# main.net
KiCad netlist of a schematic drawn in Altium Designer
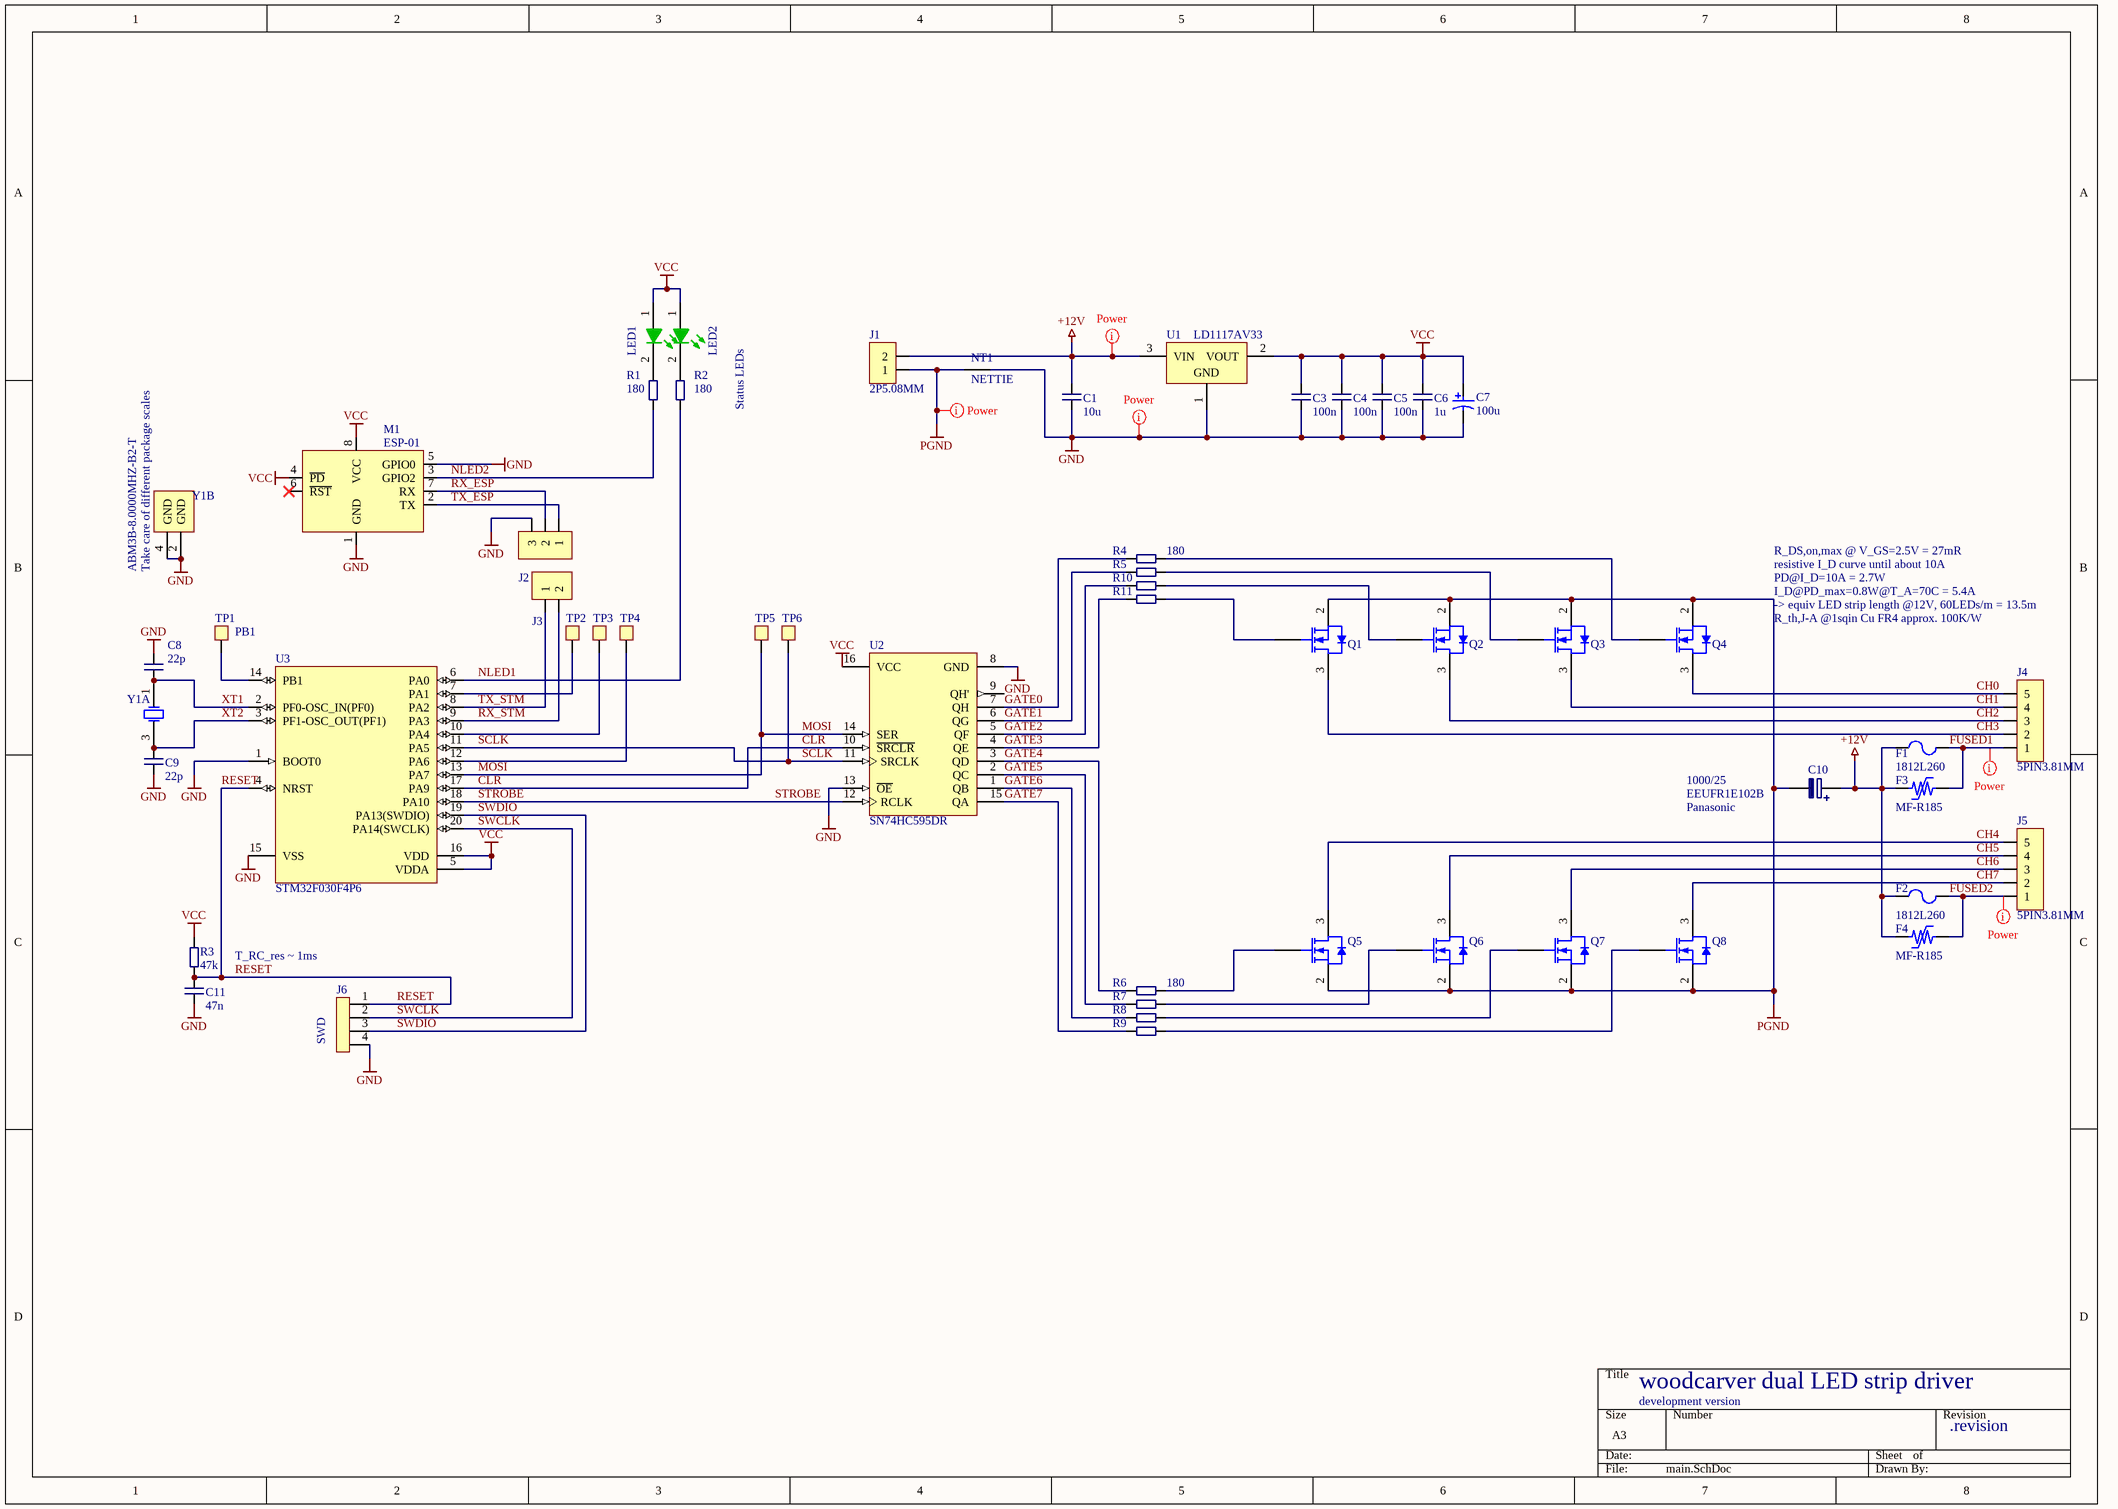
[diagram p0: main.SchDoc]

(export (version "E")
  (design (tool "Eeschema 10.0.6"))
  (components
    (comp (ref "C1")
      (value "10u")
      (footprint "6-0805_M")
      (description "Capacitor")
      (libsource (lib "components") (part "C"))
    )
    (comp (ref "C3")
      (value "100n")
      (footprint "J1-0603")
      (description "Capacitor")
      (libsource (lib "components") (part "C"))
    )
    (comp (ref "C4")
      (value "100n")
      (footprint "J1-0603")
      (description "Capacitor")
      (libsource (lib "components") (part "C"))
    )
    (comp (ref "C5")
      (value "100n")
      (footprint "J1-0603")
      (description "Capacitor")
      (libsource (lib "components") (part "C"))
    )
    (comp (ref "C6")
      (value "1u")
      (footprint "6-0805_M")
      (description "Capacitor")
      (libsource (lib "components") (part "C"))
    )
    (comp (ref "C7")
      (value "100u")
      (footprint "FHTE-8-AA07-2_L")
      (fields
        (field (name "MANUFACTURER") "Fenghuang Technology")
        (field (name "PARTNUMBER") "8471LCJAA07WPN081T")
        (field (name "TOLERANCE") "+/- 5%")
      )
      (libsource (lib "Altium Content Vault") (part "FHTE-CAP-P-2"))
    )
    (comp (ref "C8")
      (value "22p")
      (footprint "J1-0603")
      (description "Capacitor")
      (libsource (lib "components") (part "C"))
    )
    (comp (ref "C9")
      (value "22p")
      (footprint "J1-0603")
      (description "Capacitor")
      (libsource (lib "components") (part "C"))
    )
    (comp (ref "C10")
      (value "1000/25")
      (footprint "ELKO_10MM_RM5_SIDE_25MM")
      (fields (field (name "MFG PART NO") "EEUFR1E102B") (field (name "MFG") "Panasonic"))
      (libsource (lib "components") (part "ELKO"))
    )
    (comp (ref "C11")
      (value "47n")
      (footprint "J1-0603")
      (description "Capacitor")
      (libsource (lib "components") (part "C"))
    )
    (comp (ref "F1")
      (value "1812L260")
      (footprint "LFUS-FUSE1812-71_V")
      (description "Resettable PTC, 1812, 1.5 A Ihold, 3.0 A Itrip")
      (fields (field (name "PARTNUMBER") "1812L150ZR"))
      (libsource (lib "Altium Content Vault") (part "LFUS-FUSE-2"))
    )
    (comp (ref "F2")
      (value "1812L260")
      (footprint "LFUS-FUSE1812-71_V")
      (description "Resettable PTC, 1812, 1.5 A Ihold, 3.0 A Itrip")
      (fields (field (name "PARTNUMBER") "1812L150ZR"))
      (libsource (lib "Altium Content Vault") (part "LFUS-FUSE-2"))
    )
    (comp (ref "F3")
      (value "MF-R185")
      (footprint "BOUR-MF-R185")
      (description "PTC Resettable Fuse, 30 V, 40 A, -40 to 85 degC, 2-Pin THD, RoHS, Bulk")
      (fields (field (name "MANUFACTURER") "Bourns"))
      (libsource (lib "Altium Content Vault") (part "PPTC-2"))
    )
    (comp (ref "F4")
      (value "MF-R185")
      (footprint "BOUR-MF-R185")
      (description "PTC Resettable Fuse, 30 V, 40 A, -40 to 85 degC, 2-Pin THD, RoHS, Bulk")
      (fields (field (name "MANUFACTURER") "Bourns"))
      (libsource (lib "Altium Content Vault") (part "PPTC-2"))
    )
    (comp (ref "J1")
      (value "2P5.08MM")
      (footprint "HEADER_2PIN_RM5.08MM_PLUGGABLE")
      (description "Pluggable Header 2 Pin RM 5.08mm ~15A")
      (libsource (lib "components") (part "PHD2P5.08RM"))
    )
    (comp (ref "J2")
      (value "PINHD_1x3_2.54MM")
      (footprint "PINHD_3X1_2.54MM")
      (description "Pin Header 1 row 3 pin RM 2.54mm")
      (libsource (lib "components") (part "PINHD1X3"))
    )
    (comp (ref "J3")
      (value "PINHD_1x2_2.54MM")
      (footprint "PINHD_2X1_2.54MM")
      (description "Pin Header 1 row 2 pin RM 2.54mm")
      (libsource (lib "components") (part "PINHD1X2"))
    )
    (comp (ref "J4")
      (value "5PIN3.81MM")
      (footprint "HEADER_5PIN_RM3.81MM_PLUGGABLE")
      (description "Pluggable Header 5 Pin RM 3.81mm ~8A")
      (libsource (lib "components") (part "PHD5P3.81RM"))
    )
    (comp (ref "J5")
      (value "5PIN3.81MM")
      (footprint "HEADER_5PIN_RM3.81MM_PLUGGABLE")
      (description "Pluggable Header 5 Pin RM 3.81mm ~8A")
      (libsource (lib "components") (part "PHD5P3.81RM"))
    )
    (comp (ref "J6")
      (value "SWD")
      (footprint "PINHD_4X1_2.54MM")
      (description "Pin Header 4x1 pin")
      (libsource (lib "components") (part "PH_4x1"))
    )
    (comp (ref "LED1")
      (value "KP-1608MGC")
      (footprint "KING-0603LED_GREEN_V")
      (description "LED, SMT, 0603(1608), 1.1mm thickness, Green")
      (fields (field (name "MANUFACTURER") "Kingbright"))
      (libsource (lib "components") (part "CMP-0404-00001-1"))
    )
    (comp (ref "LED2")
      (value "KP-1608MGC")
      (footprint "KING-0603LED_GREEN_V")
      (description "LED, SMT, 0603(1608), 1.1mm thickness, Green")
      (fields (field (name "MANUFACTURER") "Kingbright"))
      (libsource (lib "components") (part "CMP-0404-00001-1"))
    )
    (comp (ref "M1")
      (value "ESP-01")
      (footprint "ESP01")
      (description "ESP-01 ESP8266 Wifi Module")
      (libsource (lib "components") (part "ESP01"))
    )
    (comp (ref "NT1") (value "NETTIE") (footprint "NETTIE") (libsource (lib "components") (part "NETTIE")))
    (comp (ref "Q1")
      (value "IRLML6244TRPbF")
      (footprint "ONSC-SOT-23-3-318-08_V")
      (description "Power MOSFET, 500 mA, 60 V, N-Channel, 3-Pin SOT-23, Pb-Free, Tape and Reel")
      (fields (field (name "MANUFACTURER") "On Semiconductor") (field (name "PARTNUMBER") "NVBF170LT1G"))
      (libsource (lib "Altium Content Vault") (part "ONSC-NMOS-G1S2D3-3"))
    )
    (comp (ref "Q2")
      (value "IRLML6244TRPbF")
      (footprint "ONSC-SOT-23-3-318-08_V")
      (description "Power MOSFET, 500 mA, 60 V, N-Channel, 3-Pin SOT-23, Pb-Free, Tape and Reel")
      (fields (field (name "MANUFACTURER") "On Semiconductor") (field (name "PARTNUMBER") "NVBF170LT1G"))
      (libsource (lib "Altium Content Vault") (part "ONSC-NMOS-G1S2D3-3"))
    )
    (comp (ref "Q3")
      (value "IRLML6244TRPbF")
      (footprint "ONSC-SOT-23-3-318-08_V")
      (description "Power MOSFET, 500 mA, 60 V, N-Channel, 3-Pin SOT-23, Pb-Free, Tape and Reel")
      (fields (field (name "MANUFACTURER") "On Semiconductor") (field (name "PARTNUMBER") "NVBF170LT1G"))
      (libsource (lib "Altium Content Vault") (part "ONSC-NMOS-G1S2D3-3"))
    )
    (comp (ref "Q4")
      (value "IRLML6244TRPbF")
      (footprint "ONSC-SOT-23-3-318-08_V")
      (description "Power MOSFET, 500 mA, 60 V, N-Channel, 3-Pin SOT-23, Pb-Free, Tape and Reel")
      (fields (field (name "MANUFACTURER") "On Semiconductor") (field (name "PARTNUMBER") "NVBF170LT1G"))
      (libsource (lib "Altium Content Vault") (part "ONSC-NMOS-G1S2D3-3"))
    )
    (comp (ref "Q5")
      (value "IRLML6244TRPbF")
      (footprint "ONSC-SOT-23-3-318-08_V")
      (description "Power MOSFET, 500 mA, 60 V, N-Channel, 3-Pin SOT-23, Pb-Free, Tape and Reel")
      (fields (field (name "MANUFACTURER") "On Semiconductor") (field (name "PARTNUMBER") "NVBF170LT1G"))
      (libsource (lib "Altium Content Vault") (part "ONSC-NMOS-G1S2D3-3"))
    )
    (comp (ref "Q6")
      (value "IRLML6244TRPbF")
      (footprint "ONSC-SOT-23-3-318-08_V")
      (description "Power MOSFET, 500 mA, 60 V, N-Channel, 3-Pin SOT-23, Pb-Free, Tape and Reel")
      (fields (field (name "MANUFACTURER") "On Semiconductor") (field (name "PARTNUMBER") "NVBF170LT1G"))
      (libsource (lib "Altium Content Vault") (part "ONSC-NMOS-G1S2D3-3"))
    )
    (comp (ref "Q7")
      (value "IRLML6244TRPbF")
      (footprint "ONSC-SOT-23-3-318-08_V")
      (description "Power MOSFET, 500 mA, 60 V, N-Channel, 3-Pin SOT-23, Pb-Free, Tape and Reel")
      (fields (field (name "MANUFACTURER") "On Semiconductor") (field (name "PARTNUMBER") "NVBF170LT1G"))
      (libsource (lib "Altium Content Vault") (part "ONSC-NMOS-G1S2D3-3"))
    )
    (comp (ref "Q8")
      (value "IRLML6244TRPbF")
      (footprint "ONSC-SOT-23-3-318-08_V")
      (description "Power MOSFET, 500 mA, 60 V, N-Channel, 3-Pin SOT-23, Pb-Free, Tape and Reel")
      (fields (field (name "MANUFACTURER") "On Semiconductor") (field (name "PARTNUMBER") "NVBF170LT1G"))
      (libsource (lib "Altium Content Vault") (part "ONSC-NMOS-G1S2D3-3"))
    )
    (comp (ref "R1")
      (value "180")
      (footprint "J1-0603")
      (description "Resistor")
      (libsource (lib "components") (part "R"))
    )
    (comp (ref "R2")
      (value "180")
      (footprint "J1-0603")
      (description "Resistor")
      (libsource (lib "components") (part "R"))
    )
    (comp (ref "R3")
      (value "47k")
      (footprint "J1-0603")
      (description "Resistor")
      (libsource (lib "components") (part "R"))
    )
    (comp (ref "R4")
      (value "180")
      (footprint "J1-0603")
      (description "Resistor")
      (libsource (lib "components") (part "R"))
    )
    (comp (ref "R5")
      (value "180")
      (footprint "J1-0603")
      (description "Resistor")
      (libsource (lib "components") (part "R"))
    )
    (comp (ref "R6")
      (value "180")
      (footprint "J1-0603")
      (description "Resistor")
      (libsource (lib "components") (part "R"))
    )
    (comp (ref "R7")
      (value "180")
      (footprint "J1-0603")
      (description "Resistor")
      (libsource (lib "components") (part "R"))
    )
    (comp (ref "R8")
      (value "180")
      (footprint "J1-0603")
      (description "Resistor")
      (libsource (lib "components") (part "R"))
    )
    (comp (ref "R9")
      (value "180")
      (footprint "J1-0603")
      (description "Resistor")
      (libsource (lib "components") (part "R"))
    )
    (comp (ref "R10")
      (value "180")
      (footprint "J1-0603")
      (description "Resistor")
      (libsource (lib "components") (part "R"))
    )
    (comp (ref "R11")
      (value "180")
      (footprint "J1-0603")
      (description "Resistor")
      (libsource (lib "components") (part "R"))
    )
    (comp (ref "TP1")
      (value "PB1")
      (footprint "TESTPOINT_2mm")
      (description "Testpoint")
      (libsource (lib "components") (part "TESTPOINT"))
    )
    (comp (ref "TP2")
      (value "PA1")
      (footprint "TESTPOINT_2mm")
      (description "Testpoint")
      (libsource (lib "components") (part "TESTPOINT"))
    )
    (comp (ref "TP3")
      (value "PA4")
      (footprint "TESTPOINT_2mm")
      (description "Testpoint")
      (libsource (lib "components") (part "TESTPOINT"))
    )
    (comp (ref "TP4")
      (value "PA6")
      (footprint "TESTPOINT_2mm")
      (description "Testpoint")
      (libsource (lib "components") (part "TESTPOINT"))
    )
    (comp (ref "TP5")
      (value "PA6")
      (footprint "TESTPOINT_2mm")
      (description "Testpoint")
      (libsource (lib "components") (part "TESTPOINT"))
    )
    (comp (ref "TP6")
      (value "PA6")
      (footprint "TESTPOINT_2mm")
      (description "Testpoint")
      (libsource (lib "components") (part "TESTPOINT"))
    )
    (comp (ref "U1")
      (value "LD1117AV33")
      (footprint "TO220")
      (description "1A, Low Drop Positive Voltage Regulator, 3.3V, 3-Pin TO-220")
      (libsource (lib "Altium Content Vault") (part "PM-REG-LD1117V-SIL3"))
    )
    (comp (ref "U2")
      (value "SN74HC595DR")
      (footprint "D0016A_M")
      (description "8-Bit Shift Registers With 3-State Output Registers, D0016A, LARGE T&R")
      (fields
        (field (name "GENERIC PART NUMBER") "SN74HC595")
        (field (name "MANUFACTURER") "Texas Instruments")
      )
      (libsource (lib "Altium Content Vault") (part "CMP-0780-00037-3"))
    )
    (comp (ref "U3")
      (value "STM32F030F4P6")
      (footprint "STM-TSSOP20_L")
      (libsource (lib "Altium Content Vault") (part "MC-ARM-STM32F030-IL20"))
    )
    (comp (ref "Y1")
      (value "ABM3B-8.0000MHZ-B2-T")
      (footprint "XTAL_MJ_5x3.2")
      (description "Crystal, SMD, 25.000000MHz Stab=50ppm 18.0pF")
      (fields
        (field (name "MANUFACTURER") "Abracon")
        (field (name "PARTNUMBER") "ABM3B-25.000MHZ-B2-T")
        (field (name "NOTE") "Take care of different package scales")
      )
      (libsource (lib "components") (part "ABRA-ABM3B-4"))
    )
  )
  (nets
    (net (code "1") (name "+12V") (class "Default")
      (node (ref "C1") (pin "1") (pinfunction "1_1") (pintype "passive"))
      (node (ref "C10") (pin "1") (pinfunction "1_1") (pintype "passive"))
      (node (ref "F1") (pin "1") (pinfunction "1_1") (pintype "passive"))
      (node (ref "F2") (pin "1") (pinfunction "1_1") (pintype "passive"))
      (node (ref "F3") (pin "1") (pinfunction "1_1") (pintype "passive"))
      (node (ref "F4") (pin "1") (pinfunction "1_1") (pintype "passive"))
      (node (ref "J1") (pin "2") (pinfunction "2_2") (pintype "passive"))
      (node (ref "U1") (pin "3") (pinfunction "VIN_3") (pintype "power_in"))
    )
    (net (code "2") (name "/CH0") (class "Default")
      (node (ref "J4") (pin "5") (pinfunction "5_5") (pintype "passive"))
      (node (ref "Q4") (pin "3") (pinfunction "D_3") (pintype "passive"))
    )
    (net (code "3") (name "/CH1") (class "Default")
      (node (ref "J4") (pin "4") (pinfunction "4_4") (pintype "passive"))
      (node (ref "Q3") (pin "3") (pinfunction "D_3") (pintype "passive"))
    )
    (net (code "4") (name "/CH2") (class "Default")
      (node (ref "J4") (pin "3") (pinfunction "3_3") (pintype "passive"))
      (node (ref "Q2") (pin "3") (pinfunction "D_3") (pintype "passive"))
    )
    (net (code "5") (name "/CH3") (class "Default")
      (node (ref "J4") (pin "2") (pinfunction "2_2") (pintype "passive"))
      (node (ref "Q1") (pin "3") (pinfunction "D_3") (pintype "passive"))
    )
    (net (code "6") (name "/CH4") (class "Default")
      (node (ref "J5") (pin "5") (pinfunction "5_5") (pintype "passive"))
      (node (ref "Q5") (pin "3") (pinfunction "D_3") (pintype "passive"))
    )
    (net (code "7") (name "/CH5") (class "Default")
      (node (ref "J5") (pin "4") (pinfunction "4_4") (pintype "passive"))
      (node (ref "Q6") (pin "3") (pinfunction "D_3") (pintype "passive"))
    )
    (net (code "8") (name "/CH6") (class "Default")
      (node (ref "J5") (pin "3") (pinfunction "3_3") (pintype "passive"))
      (node (ref "Q7") (pin "3") (pinfunction "D_3") (pintype "passive"))
    )
    (net (code "9") (name "/CH7") (class "Default")
      (node (ref "J5") (pin "2") (pinfunction "2_2") (pintype "passive"))
      (node (ref "Q8") (pin "3") (pinfunction "D_3") (pintype "passive"))
    )
    (net (code "10") (name "/CLR") (class "Default")
      (node (ref "U2") (pin "10") (pinfunction "~{SRCLR}_10") (pintype "input"))
      (node (ref "U3") (pin "17") (pinfunction "PA9_17") (pintype "bidirectional"))
    )
    (net (code "11") (name "/FUSED1") (class "Default")
      (node (ref "F1") (pin "2") (pinfunction "2_2") (pintype "passive"))
      (node (ref "F3") (pin "2") (pinfunction "2_2") (pintype "passive"))
      (node (ref "J4") (pin "1") (pinfunction "1_1") (pintype "passive"))
    )
    (net (code "12") (name "/FUSED2") (class "Default")
      (node (ref "F2") (pin "2") (pinfunction "2_2") (pintype "passive"))
      (node (ref "F4") (pin "2") (pinfunction "2_2") (pintype "passive"))
      (node (ref "J5") (pin "1") (pinfunction "1_1") (pintype "passive"))
    )
    (net (code "13") (name "/GATE0") (class "Default")
      (node (ref "R4") (pin "2") (pinfunction "2_2") (pintype "passive"))
      (node (ref "U2") (pin "7") (pinfunction "QH_7") (pintype "tri_state"))
    )
    (net (code "14") (name "/GATE1") (class "Default")
      (node (ref "R5") (pin "2") (pinfunction "2_2") (pintype "passive"))
      (node (ref "U2") (pin "6") (pinfunction "QG_6") (pintype "tri_state"))
    )
    (net (code "15") (name "/GATE2") (class "Default")
      (node (ref "R10") (pin "2") (pinfunction "2_2") (pintype "passive"))
      (node (ref "U2") (pin "5") (pinfunction "QF_5") (pintype "tri_state"))
    )
    (net (code "16") (name "/GATE3") (class "Default")
      (node (ref "R11") (pin "2") (pinfunction "2_2") (pintype "passive"))
      (node (ref "U2") (pin "4") (pinfunction "QE_4") (pintype "tri_state"))
    )
    (net (code "17") (name "/GATE4") (class "Default")
      (node (ref "R6") (pin "2") (pinfunction "2_2") (pintype "passive"))
      (node (ref "U2") (pin "3") (pinfunction "QD_3") (pintype "tri_state"))
    )
    (net (code "18") (name "/GATE5") (class "Default")
      (node (ref "R7") (pin "2") (pinfunction "2_2") (pintype "passive"))
      (node (ref "U2") (pin "2") (pinfunction "QC_2") (pintype "tri_state"))
    )
    (net (code "19") (name "/GATE6") (class "Default")
      (node (ref "R8") (pin "2") (pinfunction "2_2") (pintype "passive"))
      (node (ref "U2") (pin "1") (pinfunction "QB_1") (pintype "tri_state"))
    )
    (net (code "20") (name "/GATE7") (class "Default")
      (node (ref "R9") (pin "2") (pinfunction "2_2") (pintype "passive"))
      (node (ref "U2") (pin "15") (pinfunction "QA_15") (pintype "tri_state"))
    )
    (net (code "21") (name "/MOSI") (class "Default")
      (node (ref "TP5") (pin "1") (pinfunction "1_1") (pintype "passive"))
      (node (ref "U2") (pin "14") (pinfunction "SER_14") (pintype "input"))
      (node (ref "U3") (pin "13") (pinfunction "PA7_13") (pintype "bidirectional"))
    )
    (net (code "22") (name "/NLED1") (class "Default")
      (node (ref "R2") (pin "1") (pinfunction "1_1") (pintype "passive"))
      (node (ref "U3") (pin "6") (pinfunction "PA0_6") (pintype "bidirectional"))
    )
    (net (code "23") (name "/NLED2") (class "Default")
      (node (ref "M1") (pin "3") (pinfunction "GPIO2_3") (pintype "passive"))
      (node (ref "R1") (pin "1") (pinfunction "1_1") (pintype "passive"))
    )
    (net (code "24") (name "/RESET") (class "Default")
      (node (ref "C11") (pin "1") (pinfunction "1_1") (pintype "passive"))
      (node (ref "J6") (pin "1") (pinfunction "1_1") (pintype "passive"))
      (node (ref "R3") (pin "1") (pinfunction "1_1") (pintype "passive"))
      (node (ref "U3") (pin "4") (pinfunction "NRST_4") (pintype "bidirectional"))
    )
    (net (code "25") (name "/RX_ESP") (class "Default")
      (node (ref "J2") (pin "2") (pinfunction "2_2") (pintype "passive"))
      (node (ref "M1") (pin "7") (pinfunction "RX_7") (pintype "passive"))
    )
    (net (code "26") (name "/RX_STM") (class "Default")
      (node (ref "J3") (pin "2") (pinfunction "2_2") (pintype "passive"))
      (node (ref "U3") (pin "9") (pinfunction "PA3_9") (pintype "bidirectional"))
    )
    (net (code "27") (name "/SCLK") (class "Default")
      (node (ref "TP6") (pin "1") (pinfunction "1_1") (pintype "passive"))
      (node (ref "U2") (pin "11") (pinfunction "SRCLK_11") (pintype "input"))
      (node (ref "U3") (pin "11") (pinfunction "PA5_11") (pintype "bidirectional"))
    )
    (net (code "28") (name "/STROBE") (class "Default")
      (node (ref "U2") (pin "12") (pinfunction "RCLK_12") (pintype "input"))
      (node (ref "U3") (pin "18") (pinfunction "PA10_18") (pintype "bidirectional"))
    )
    (net (code "29") (name "/SWCLK") (class "Default")
      (node (ref "J6") (pin "2") (pinfunction "2_2") (pintype "passive"))
      (node (ref "U3") (pin "20") (pinfunction "PA14(SWCLK)_20") (pintype "bidirectional"))
    )
    (net (code "30") (name "/SWDIO") (class "Default")
      (node (ref "J6") (pin "3") (pinfunction "3_3") (pintype "passive"))
      (node (ref "U3") (pin "19") (pinfunction "PA13(SWDIO)_19") (pintype "bidirectional"))
    )
    (net (code "31") (name "/TX_ESP") (class "Default")
      (node (ref "J2") (pin "1") (pinfunction "1_1") (pintype "passive"))
      (node (ref "M1") (pin "2") (pinfunction "TX_2") (pintype "passive"))
    )
    (net (code "32") (name "/TX_STM") (class "Default")
      (node (ref "J3") (pin "1") (pinfunction "1_1") (pintype "passive"))
      (node (ref "U3") (pin "8") (pinfunction "PA2_8") (pintype "bidirectional"))
    )
    (net (code "33") (name "/XT1") (class "Default")
      (node (ref "C8") (pin "2") (pinfunction "2_2") (pintype "passive"))
      (node (ref "U3") (pin "2") (pinfunction "PF0-OSC_IN(PF0)_2") (pintype "bidirectional"))
      (node (ref "Y1") (pin "1") (pinfunction "X1_1") (pintype "passive"))
    )
    (net (code "34") (name "/XT2") (class "Default")
      (node (ref "C9") (pin "1") (pinfunction "1_1") (pintype "passive"))
      (node (ref "U3") (pin "3") (pinfunction "PF1-OSC_OUT(PF1)_3") (pintype "bidirectional"))
      (node (ref "Y1") (pin "3") (pinfunction "X2_3") (pintype "passive"))
    )
    (net (code "35") (name "GND") (class "Default")
      (node (ref "C1") (pin "2") (pinfunction "2_2") (pintype "passive"))
      (node (ref "C11") (pin "2") (pinfunction "2_2") (pintype "passive"))
      (node (ref "C3") (pin "2") (pinfunction "2_2") (pintype "passive"))
      (node (ref "C4") (pin "2") (pinfunction "2_2") (pintype "passive"))
      (node (ref "C5") (pin "2") (pinfunction "2_2") (pintype "passive"))
      (node (ref "C6") (pin "2") (pinfunction "2_2") (pintype "passive"))
      (node (ref "C7") (pin "2") (pinfunction "2_2") (pintype "passive"))
      (node (ref "C8") (pin "1") (pinfunction "1_1") (pintype "passive"))
      (node (ref "C9") (pin "2") (pinfunction "2_2") (pintype "passive"))
      (node (ref "J2") (pin "3") (pinfunction "3_3") (pintype "passive"))
      (node (ref "J6") (pin "4") (pinfunction "4_4") (pintype "passive"))
      (node (ref "M1") (pin "1") (pinfunction "GND_1") (pintype "passive"))
      (node (ref "M1") (pin "5") (pinfunction "GPIO0_5") (pintype "passive"))
      (node (ref "NT1") (pin "2") (pinfunction "2_2") (pintype "passive"))
      (node (ref "U1") (pin "1") (pinfunction "GND_1") (pintype "power_in"))
      (node (ref "U2") (pin "13") (pinfunction "~{OE}_13") (pintype "input"))
      (node (ref "U2") (pin "8") (pinfunction "GND_8") (pintype "power_in"))
      (node (ref "U3") (pin "1") (pinfunction "BOOT0_1") (pintype "input"))
      (node (ref "U3") (pin "15") (pinfunction "VSS_15") (pintype "power_in"))
      (node (ref "Y1") (pin "2") (pinfunction "GND_2") (pintype "power_in"))
      (node (ref "Y1") (pin "4") (pinfunction "GND_4") (pintype "power_in"))
    )
    (net (code "36") (name "Net-(LED1-K)") (class "Default")
      (node (ref "LED1") (pin "2") (pinfunction "K_2") (pintype "passive"))
      (node (ref "R1") (pin "2") (pinfunction "2_2") (pintype "passive"))
    )
    (net (code "37") (name "Net-(LED2-K)") (class "Default")
      (node (ref "LED2") (pin "2") (pinfunction "K_2") (pintype "passive"))
      (node (ref "R2") (pin "2") (pinfunction "2_2") (pintype "passive"))
    )
    (net (code "38") (name "Net-(Q1-G)") (class "Default")
      (node (ref "Q1") (pin "1") (pinfunction "G_1") (pintype "passive"))
      (node (ref "R11") (pin "1") (pinfunction "1_1") (pintype "passive"))
    )
    (net (code "39") (name "Net-(Q2-G)") (class "Default")
      (node (ref "Q2") (pin "1") (pinfunction "G_1") (pintype "passive"))
      (node (ref "R10") (pin "1") (pinfunction "1_1") (pintype "passive"))
    )
    (net (code "40") (name "Net-(Q3-G)") (class "Default")
      (node (ref "Q3") (pin "1") (pinfunction "G_1") (pintype "passive"))
      (node (ref "R5") (pin "1") (pinfunction "1_1") (pintype "passive"))
    )
    (net (code "41") (name "Net-(Q4-G)") (class "Default")
      (node (ref "Q4") (pin "1") (pinfunction "G_1") (pintype "passive"))
      (node (ref "R4") (pin "1") (pinfunction "1_1") (pintype "passive"))
    )
    (net (code "42") (name "Net-(Q5-G)") (class "Default")
      (node (ref "Q5") (pin "1") (pinfunction "G_1") (pintype "passive"))
      (node (ref "R6") (pin "1") (pinfunction "1_1") (pintype "passive"))
    )
    (net (code "43") (name "Net-(Q6-G)") (class "Default")
      (node (ref "Q6") (pin "1") (pinfunction "G_1") (pintype "passive"))
      (node (ref "R7") (pin "1") (pinfunction "1_1") (pintype "passive"))
    )
    (net (code "44") (name "Net-(Q7-G)") (class "Default")
      (node (ref "Q7") (pin "1") (pinfunction "G_1") (pintype "passive"))
      (node (ref "R8") (pin "1") (pinfunction "1_1") (pintype "passive"))
    )
    (net (code "45") (name "Net-(Q8-G)") (class "Default")
      (node (ref "Q8") (pin "1") (pinfunction "G_1") (pintype "passive"))
      (node (ref "R9") (pin "1") (pinfunction "1_1") (pintype "passive"))
    )
    (net (code "46") (name "Net-(U3-PA1)") (class "Default")
      (node (ref "TP2") (pin "1") (pinfunction "1_1") (pintype "passive"))
      (node (ref "U3") (pin "7") (pinfunction "PA1_7") (pintype "bidirectional"))
    )
    (net (code "47") (name "Net-(U3-PA4)") (class "Default")
      (node (ref "TP3") (pin "1") (pinfunction "1_1") (pintype "passive"))
      (node (ref "U3") (pin "10") (pinfunction "PA4_10") (pintype "bidirectional"))
    )
    (net (code "48") (name "Net-(U3-PA6)") (class "Default")
      (node (ref "TP4") (pin "1") (pinfunction "1_1") (pintype "passive"))
      (node (ref "U3") (pin "12") (pinfunction "PA6_12") (pintype "bidirectional"))
    )
    (net (code "49") (name "Net-(U3-PB1)") (class "Default")
      (node (ref "TP1") (pin "1") (pinfunction "1_1") (pintype "passive"))
      (node (ref "U3") (pin "14") (pinfunction "PB1_14") (pintype "bidirectional"))
    )
    (net (code "50") (name "PGND") (class "Default")
      (node (ref "C10") (pin "2") (pinfunction "2_2") (pintype "passive"))
      (node (ref "J1") (pin "1") (pinfunction "1_1") (pintype "passive"))
      (node (ref "NT1") (pin "1") (pinfunction "1_1") (pintype "passive"))
      (node (ref "Q1") (pin "2") (pinfunction "S_2") (pintype "passive"))
      (node (ref "Q2") (pin "2") (pinfunction "S_2") (pintype "passive"))
      (node (ref "Q3") (pin "2") (pinfunction "S_2") (pintype "passive"))
      (node (ref "Q4") (pin "2") (pinfunction "S_2") (pintype "passive"))
      (node (ref "Q5") (pin "2") (pinfunction "S_2") (pintype "passive"))
      (node (ref "Q6") (pin "2") (pinfunction "S_2") (pintype "passive"))
      (node (ref "Q7") (pin "2") (pinfunction "S_2") (pintype "passive"))
      (node (ref "Q8") (pin "2") (pinfunction "S_2") (pintype "passive"))
    )
    (net (code "51") (name "VCC") (class "Default")
      (node (ref "C3") (pin "1") (pinfunction "1_1") (pintype "passive"))
      (node (ref "C4") (pin "1") (pinfunction "1_1") (pintype "passive"))
      (node (ref "C5") (pin "1") (pinfunction "1_1") (pintype "passive"))
      (node (ref "C6") (pin "1") (pinfunction "1_1") (pintype "passive"))
      (node (ref "C7") (pin "1") (pinfunction "1_1") (pintype "passive"))
      (node (ref "LED1") (pin "1") (pinfunction "A_1") (pintype "passive"))
      (node (ref "LED2") (pin "1") (pinfunction "A_1") (pintype "passive"))
      (node (ref "M1") (pin "4") (pinfunction "~{PD}_4") (pintype "passive"))
      (node (ref "M1") (pin "8") (pinfunction "VCC_8") (pintype "passive"))
      (node (ref "R3") (pin "2") (pinfunction "2_2") (pintype "passive"))
      (node (ref "U1") (pin "2") (pinfunction "VOUT_2") (pintype "power_in"))
      (node (ref "U2") (pin "16") (pinfunction "VCC_16") (pintype "power_in"))
      (node (ref "U3") (pin "16") (pinfunction "VDD_16") (pintype "power_in"))
      (node (ref "U3") (pin "5") (pinfunction "VDDA_5") (pintype "power_in"))
    )
    (net (code "52") (name "unconnected-(M1-~{RST}-Pad6)") (class "Default")
      (node (ref "M1") (pin "6") (pinfunction "~{RST}_6") (pintype "passive+no_connect"))
    )
    (net (code "53") (name "unconnected-(U2-QH'-Pad9)") (class "Default")
      (node (ref "U2") (pin "9") (pinfunction "QH'_9") (pintype "output"))
    )
  )
)
